# LTE.net
KiCad netlist of a schematic drawn in Altium Designer
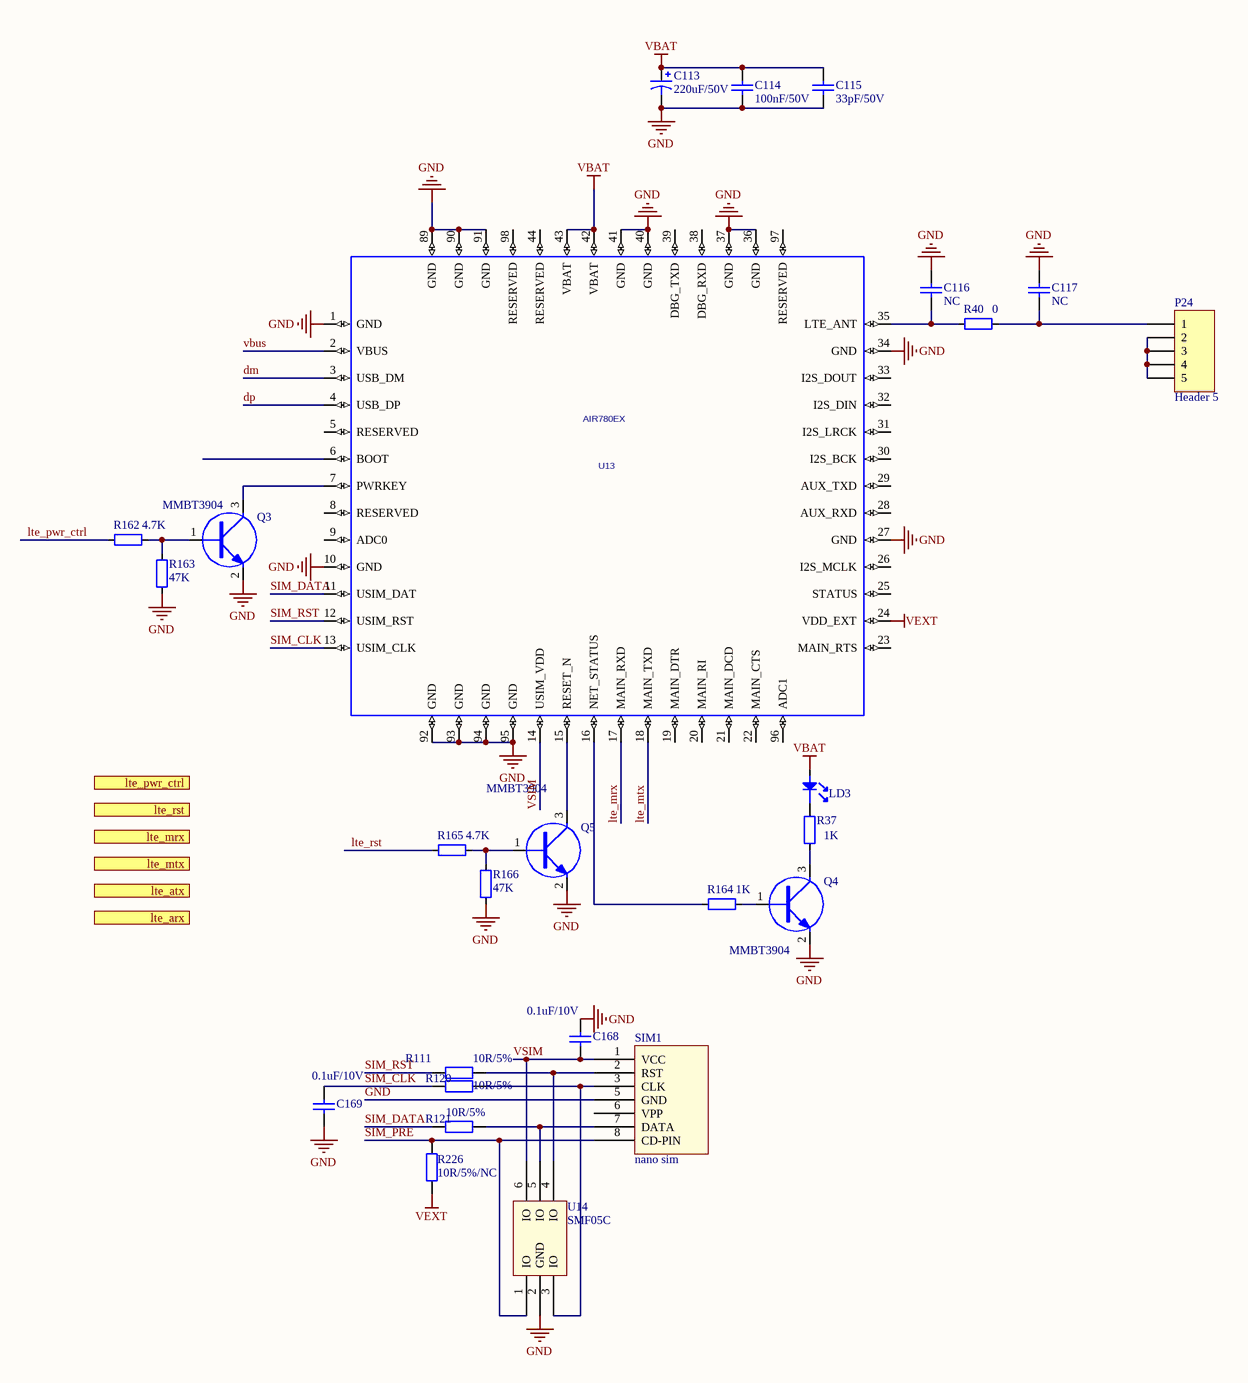
[diagram p0: LTE.SchDoc]

(export (version "E")
  (design (tool "Eeschema 10.0.6"))
  (components
    (comp (ref "C113")
      (value "220uF/50V")
      (footprint "Φ10×10")
      (description "Polarized Capacitor (Radial)")
      (fields (field (name "PUBLISHER") "Altium Limited"))
      (libsource (lib "Miscellaneous Devices") (part "Cap Pol1"))
    )
    (comp (ref "C114")
      (value "100nF/50V")
      (footprint "0603C")
      (description "Capacitor")
      (fields (field (name "PUBLISHER") "Altium Limited"))
      (libsource (lib "Miscellaneous Devices") (part "Cap"))
    )
    (comp (ref "C115")
      (value "33pF/50V")
      (footprint "0603C")
      (description "Capacitor")
      (fields (field (name "PUBLISHER") "Altium Limited"))
      (libsource (lib "Miscellaneous Devices") (part "Cap"))
    )
    (comp (ref "C116")
      (value "NC")
      (footprint "0603c")
      (description "Capacitor")
      (fields (field (name "PUBLISHER") "Altium Limited"))
      (libsource (lib "Miscellaneous Devices") (part "Cap"))
    )
    (comp (ref "C117")
      (value "NC")
      (footprint "0603c")
      (description "Capacitor")
      (fields (field (name "PUBLISHER") "Altium Limited"))
      (libsource (lib "Miscellaneous Devices") (part "Cap"))
    )
    (comp (ref "C168")
      (value "0.1uF/10V")
      (footprint "0603c")
      (description "Capacitor")
      (fields (field (name "PUBLISHER") "Altium Limited"))
      (libsource (lib "Miscellaneous Devices") (part "Cap"))
    )
    (comp (ref "C169")
      (value "0.1uF/10V")
      (footprint "0603c")
      (description "Capacitor")
      (fields (field (name "PUBLISHER") "Altium Limited"))
      (libsource (lib "Miscellaneous Devices") (part "Cap"))
    )
    (comp (ref "LD3")
      (value "LED_Green_19-217")
      (footprint "0603led")
      (libsource (lib "RC_M_D_00") (part "LED_Green_19-217"))
    )
    (comp (ref "P24")
      (value "Header 5")
      (footprint "KH-SMA-KE-Z")
      (description "Header, 5-Pin")
      (fields (field (name "PUBLISHER") "Altium Limited"))
      (libsource (lib "Miscellaneous Connectors") (part "Header 5"))
    )
    (comp (ref "Q3")
      (value "MMBT3904")
      (footprint "SOT23-3")
      (libsource (lib "CenLib") (part "NPN_MMBT3904"))
    )
    (comp (ref "Q4")
      (value "MMBT3904")
      (footprint "SOT23-3")
      (libsource (lib "CenLib") (part "NPN_MMBT3904"))
    )
    (comp (ref "Q5")
      (value "MMBT3904")
      (footprint "SOT23-3")
      (libsource (lib "CenLib") (part "NPN_MMBT3904"))
    )
    (comp (ref "R37") (value "1K") (footprint "0603R") (libsource (lib "RC_M_D_00") (part "RES0603")))
    (comp (ref "R40") (value "0") (footprint "0603r") (libsource (lib "RC_M_D_00") (part "RES0603")))
    (comp (ref "R111")
      (value "10R/5%")
      (footprint "0603r")
      (description "Resistor")
      (fields (field (name "PUBLISHER") "Altium Limited"))
      (libsource (lib "") (part "Res2_1"))
    )
    (comp (ref "R120")
      (value "10R/5%")
      (footprint "0603r")
      (description "Resistor")
      (fields (field (name "PUBLISHER") "Altium Limited"))
      (libsource (lib "") (part "Res2_1"))
    )
    (comp (ref "R121")
      (value "10R/5%")
      (footprint "0603r")
      (description "Resistor")
      (fields (field (name "PUBLISHER") "Altium Limited"))
      (libsource (lib "") (part "Res2_1"))
    )
    (comp (ref "R162") (value "4.7K") (footprint "0603R") (libsource (lib "RC_M_D_00") (part "RES0603")))
    (comp (ref "R163") (value "47K") (footprint "0603r") (libsource (lib "RC_M_D_00") (part "RES0603")))
    (comp (ref "R164") (value "1K") (footprint "0603r") (libsource (lib "RC_M_D_00") (part "RES0603")))
    (comp (ref "R165") (value "4.7K") (footprint "0603R") (libsource (lib "RC_M_D_00") (part "RES0603")))
    (comp (ref "R166") (value "47K") (footprint "0603r") (libsource (lib "RC_M_D_00") (part "RES0603")))
    (comp (ref "R226")
      (value "10R/5%/NC")
      (footprint "0603r")
      (description "Resistor")
      (fields (field (name "PUBLISHER") "Altium Limited"))
      (libsource (lib "Miscellaneous Devices") (part "Res2"))
    )
    (comp (ref "SIM1") (value "nano sim") (footprint "Nano SIM") (libsource (lib "lm") (part "nano sim")))
    (comp (ref "U13")
      (value "AIR780EX")
      (footprint "Air780EX_AD:AIR780EX")
      (libsource (lib "*") (part "AIR780EX"))
    )
    (comp (ref "U14") (value "SMF05C") (footprint "sc70-6l") (libsource (lib "lm") (part "SMF05C")))
  )
  (nets
    (net (code "1") (name "/SIM_CLK") (class "Default")
      (node (ref "C169") (pin "1") (pinfunction "1_1") (pintype "passive"))
      (node (ref "R120") (pin "2") (pinfunction "2_2") (pintype "passive"))
      (node (ref "U13") (pin "13") (pinfunction "USIM_CLK_13") (pintype "bidirectional"))
    )
    (net (code "2") (name "/SIM_DATA") (class "Default")
      (node (ref "R121") (pin "2") (pinfunction "2_2") (pintype "passive"))
      (node (ref "U13") (pin "11") (pinfunction "USIM_DAT_11") (pintype "bidirectional"))
    )
    (net (code "3") (name "/SIM_PRE") (class "Default")
      (node (ref "R226") (pin "1") (pinfunction "1_1") (pintype "passive"))
      (node (ref "SIM1") (pin "8") (pinfunction "CD-PIN_8") (pintype "passive"))
      (node (ref "U14") (pin "1") (pinfunction "IO_1") (pintype "passive"))
    )
    (net (code "4") (name "/SIM_RST") (class "Default")
      (node (ref "R111") (pin "2") (pinfunction "2_2") (pintype "passive"))
      (node (ref "U13") (pin "12") (pinfunction "USIM_RST_12") (pintype "bidirectional"))
    )
    (net (code "5") (name "/VSIM") (class "Default")
      (node (ref "C168") (pin "2") (pinfunction "2_2") (pintype "passive"))
      (node (ref "SIM1") (pin "1") (pinfunction "VCC_1") (pintype "passive"))
      (node (ref "U13") (pin "14") (pinfunction "USIM_VDD_14") (pintype "bidirectional"))
      (node (ref "U14") (pin "6") (pinfunction "IO_6") (pintype "passive"))
    )
    (net (code "6") (name "/dm") (class "Default")
      (node (ref "U13") (pin "3") (pinfunction "USB_DM_3") (pintype "bidirectional"))
    )
    (net (code "7") (name "/dp") (class "Default")
      (node (ref "U13") (pin "4") (pinfunction "USB_DP_4") (pintype "bidirectional"))
    )
    (net (code "10") (name "/lte_mrx") (class "Default")
      (node (ref "U13") (pin "17") (pinfunction "MAIN_RXD_17") (pintype "bidirectional"))
    )
    (net (code "11") (name "/lte_mtx") (class "Default")
      (node (ref "U13") (pin "18") (pinfunction "MAIN_TXD_18") (pintype "bidirectional"))
    )
    (net (code "12") (name "/lte_pwr_ctrl") (class "Default")
      (node (ref "R162") (pin "1") (pinfunction "1_1") (pintype "passive"))
    )
    (net (code "13") (name "/lte_rst") (class "Default")
      (node (ref "R165") (pin "1") (pinfunction "1_1") (pintype "passive"))
    )
    (net (code "14") (name "/vbus") (class "Default")
      (node (ref "U13") (pin "2") (pinfunction "VBUS_2") (pintype "bidirectional"))
    )
    (net (code "15") (name "GND") (class "Default")
      (node (ref "C113") (pin "2") (pinfunction "2_2") (pintype "passive"))
      (node (ref "C114") (pin "1") (pinfunction "1_1") (pintype "passive"))
      (node (ref "C115") (pin "1") (pinfunction "1_1") (pintype "passive"))
      (node (ref "C116") (pin "2") (pinfunction "2_2") (pintype "passive"))
      (node (ref "C117") (pin "2") (pinfunction "2_2") (pintype "passive"))
      (node (ref "C168") (pin "1") (pinfunction "1_1") (pintype "passive"))
      (node (ref "C169") (pin "2") (pinfunction "2_2") (pintype "passive"))
      (node (ref "Q3") (pin "2") (pinfunction "E_2") (pintype "passive"))
      (node (ref "Q4") (pin "2") (pinfunction "E_2") (pintype "passive"))
      (node (ref "Q5") (pin "2") (pinfunction "E_2") (pintype "passive"))
      (node (ref "R163") (pin "1") (pinfunction "1_1") (pintype "passive"))
      (node (ref "R166") (pin "1") (pinfunction "1_1") (pintype "passive"))
      (node (ref "SIM1") (pin "5") (pinfunction "GND_5") (pintype "passive"))
      (node (ref "U13") (pin "1") (pinfunction "GND_1") (pintype "bidirectional"))
      (node (ref "U13") (pin "10") (pinfunction "GND_10") (pintype "bidirectional"))
      (node (ref "U13") (pin "27") (pinfunction "GND_27") (pintype "bidirectional"))
      (node (ref "U13") (pin "34") (pinfunction "GND_34") (pintype "bidirectional"))
      (node (ref "U13") (pin "36") (pinfunction "GND_36") (pintype "bidirectional"))
      (node (ref "U13") (pin "37") (pinfunction "GND_37") (pintype "bidirectional"))
      (node (ref "U13") (pin "40") (pinfunction "GND_40") (pintype "bidirectional"))
      (node (ref "U13") (pin "41") (pinfunction "GND_41") (pintype "bidirectional"))
      (node (ref "U13") (pin "89") (pinfunction "GND_89") (pintype "bidirectional"))
      (node (ref "U13") (pin "90") (pinfunction "GND_90") (pintype "bidirectional"))
      (node (ref "U13") (pin "91") (pinfunction "GND_91") (pintype "bidirectional"))
      (node (ref "U13") (pin "92") (pinfunction "GND_92") (pintype "bidirectional"))
      (node (ref "U13") (pin "93") (pinfunction "GND_93") (pintype "bidirectional"))
      (node (ref "U13") (pin "94") (pinfunction "GND_94") (pintype "bidirectional"))
      (node (ref "U13") (pin "95") (pinfunction "GND_95") (pintype "bidirectional"))
      (node (ref "U14") (pin "2") (pinfunction "GND_2") (pintype "passive"))
    )
    (net (code "16") (name "Net-(C117-Pad1)") (class "Default")
      (node (ref "C117") (pin "1") (pinfunction "1_1") (pintype "passive"))
      (node (ref "P24") (pin "1") (pinfunction "1_1") (pintype "passive"))
      (node (ref "R40") (pin "2") (pinfunction "2_2") (pintype "passive"))
    )
    (net (code "17") (name "Net-(LD3-Pad2)") (class "Default")
      (node (ref "LD3") (pin "2") (pinfunction "2_2") (pintype "passive"))
      (node (ref "R37") (pin "1") (pinfunction "1_1") (pintype "passive"))
    )
    (net (code "18") (name "Net-(P24-Pad2)") (class "Default")
      (node (ref "P24") (pin "2") (pinfunction "2_2") (pintype "passive"))
      (node (ref "P24") (pin "3") (pinfunction "3_3") (pintype "passive"))
      (node (ref "P24") (pin "4") (pinfunction "4_4") (pintype "passive"))
      (node (ref "P24") (pin "5") (pinfunction "5_5") (pintype "passive"))
    )
    (net (code "19") (name "Net-(Q3-B)") (class "Default")
      (node (ref "Q3") (pin "1") (pinfunction "B_1") (pintype "passive"))
      (node (ref "R162") (pin "2") (pinfunction "2_2") (pintype "passive"))
      (node (ref "R163") (pin "2") (pinfunction "2_2") (pintype "passive"))
    )
    (net (code "20") (name "Net-(Q3-C)") (class "Default")
      (node (ref "Q3") (pin "3") (pinfunction "C_3") (pintype "passive"))
      (node (ref "U13") (pin "7") (pinfunction "PWRKEY_7") (pintype "bidirectional"))
    )
    (net (code "21") (name "Net-(Q4-B)") (class "Default")
      (node (ref "Q4") (pin "1") (pinfunction "B_1") (pintype "passive"))
      (node (ref "R164") (pin "2") (pinfunction "2_2") (pintype "passive"))
    )
    (net (code "22") (name "Net-(Q4-C)") (class "Default")
      (node (ref "Q4") (pin "3") (pinfunction "C_3") (pintype "passive"))
      (node (ref "R37") (pin "2") (pinfunction "2_2") (pintype "passive"))
    )
    (net (code "23") (name "Net-(Q5-B)") (class "Default")
      (node (ref "Q5") (pin "1") (pinfunction "B_1") (pintype "passive"))
      (node (ref "R165") (pin "2") (pinfunction "2_2") (pintype "passive"))
      (node (ref "R166") (pin "2") (pinfunction "2_2") (pintype "passive"))
    )
    (net (code "24") (name "Net-(Q5-C)") (class "Default")
      (node (ref "Q5") (pin "3") (pinfunction "C_3") (pintype "passive"))
      (node (ref "U13") (pin "15") (pinfunction "RESET_N_15") (pintype "bidirectional"))
    )
    (net (code "25") (name "Net-(SIM1-CLK)") (class "Default")
      (node (ref "R120") (pin "1") (pinfunction "1_1") (pintype "passive"))
      (node (ref "SIM1") (pin "3") (pinfunction "CLK_3") (pintype "passive"))
      (node (ref "U14") (pin "3") (pinfunction "IO_3") (pintype "passive"))
    )
    (net (code "26") (name "Net-(SIM1-DATA)") (class "Default")
      (node (ref "R121") (pin "1") (pinfunction "1_1") (pintype "passive"))
      (node (ref "SIM1") (pin "7") (pinfunction "DATA_7") (pintype "passive"))
      (node (ref "U14") (pin "5") (pinfunction "IO_5") (pintype "passive"))
    )
    (net (code "27") (name "Net-(SIM1-RST)") (class "Default")
      (node (ref "R111") (pin "1") (pinfunction "1_1") (pintype "passive"))
      (node (ref "SIM1") (pin "2") (pinfunction "RST_2") (pintype "passive"))
      (node (ref "U14") (pin "4") (pinfunction "IO_4") (pintype "passive"))
    )
    (net (code "28") (name "Net-(U13-LTE_ANT)") (class "Default")
      (node (ref "C116") (pin "1") (pinfunction "1_1") (pintype "passive"))
      (node (ref "R40") (pin "1") (pinfunction "1_1") (pintype "passive"))
      (node (ref "U13") (pin "35") (pinfunction "LTE_ANT_35") (pintype "bidirectional"))
    )
    (net (code "29") (name "Net-(U13-NET_STATUS)") (class "Default")
      (node (ref "R164") (pin "1") (pinfunction "1_1") (pintype "passive"))
      (node (ref "U13") (pin "16") (pinfunction "NET_STATUS_16") (pintype "bidirectional"))
    )
    (net (code "30") (name "VBAT") (class "Default")
      (node (ref "C113") (pin "1") (pinfunction "1_1") (pintype "passive"))
      (node (ref "C114") (pin "2") (pinfunction "2_2") (pintype "passive"))
      (node (ref "C115") (pin "2") (pinfunction "2_2") (pintype "passive"))
      (node (ref "LD3") (pin "1") (pinfunction "1_1") (pintype "passive"))
      (node (ref "U13") (pin "42") (pinfunction "VBAT_42") (pintype "bidirectional"))
      (node (ref "U13") (pin "43") (pinfunction "VBAT_43") (pintype "bidirectional"))
    )
    (net (code "31") (name "VEXT") (class "Default")
      (node (ref "R226") (pin "2") (pinfunction "2_2") (pintype "passive"))
      (node (ref "U13") (pin "24") (pinfunction "VDD_EXT_24") (pintype "bidirectional"))
    )
    (net (code "32") (name "unconnected-(SIM1-VPP-Pad6)") (class "Default")
      (node (ref "SIM1") (pin "6") (pinfunction "VPP_6") (pintype "passive"))
    )
    (net (code "33") (name "unconnected-(U13-ADC0-Pad9)") (class "Default")
      (node (ref "U13") (pin "9") (pinfunction "ADC0_9") (pintype "bidirectional"))
    )
    (net (code "34") (name "unconnected-(U13-ADC1-Pad96)") (class "Default")
      (node (ref "U13") (pin "96") (pinfunction "ADC1_96") (pintype "bidirectional"))
    )
    (net (code "35") (name "unconnected-(U13-AUX_RXD-Pad28)") (class "Default")
      (node (ref "U13") (pin "28") (pinfunction "AUX_RXD_28") (pintype "bidirectional"))
    )
    (net (code "36") (name "unconnected-(U13-AUX_TXD-Pad29)") (class "Default")
      (node (ref "U13") (pin "29") (pinfunction "AUX_TXD_29") (pintype "bidirectional"))
    )
    (net (code "37") (name "unconnected-(U13-BOOT-Pad6)") (class "Default")
      (node (ref "U13") (pin "6") (pinfunction "BOOT_6") (pintype "bidirectional"))
    )
    (net (code "38") (name "unconnected-(U13-DBG_RXD-Pad38)") (class "Default")
      (node (ref "U13") (pin "38") (pinfunction "DBG_RXD_38") (pintype "bidirectional"))
    )
    (net (code "39") (name "unconnected-(U13-DBG_TXD-Pad39)") (class "Default")
      (node (ref "U13") (pin "39") (pinfunction "DBG_TXD_39") (pintype "bidirectional"))
    )
    (net (code "40") (name "unconnected-(U13-I2S_BCK-Pad30)") (class "Default")
      (node (ref "U13") (pin "30") (pinfunction "I2S_BCK_30") (pintype "bidirectional"))
    )
    (net (code "41") (name "unconnected-(U13-I2S_DIN-Pad32)") (class "Default")
      (node (ref "U13") (pin "32") (pinfunction "I2S_DIN_32") (pintype "bidirectional"))
    )
    (net (code "42") (name "unconnected-(U13-I2S_DOUT-Pad33)") (class "Default")
      (node (ref "U13") (pin "33") (pinfunction "I2S_DOUT_33") (pintype "bidirectional"))
    )
    (net (code "43") (name "unconnected-(U13-I2S_LRCK-Pad31)") (class "Default")
      (node (ref "U13") (pin "31") (pinfunction "I2S_LRCK_31") (pintype "bidirectional"))
    )
    (net (code "44") (name "unconnected-(U13-I2S_MCLK-Pad26)") (class "Default")
      (node (ref "U13") (pin "26") (pinfunction "I2S_MCLK_26") (pintype "bidirectional"))
    )
    (net (code "45") (name "unconnected-(U13-MAIN_CTS-Pad22)") (class "Default")
      (node (ref "U13") (pin "22") (pinfunction "MAIN_CTS_22") (pintype "bidirectional"))
    )
    (net (code "46") (name "unconnected-(U13-MAIN_DCD-Pad21)") (class "Default")
      (node (ref "U13") (pin "21") (pinfunction "MAIN_DCD_21") (pintype "bidirectional"))
    )
    (net (code "47") (name "unconnected-(U13-MAIN_DTR-Pad19)") (class "Default")
      (node (ref "U13") (pin "19") (pinfunction "MAIN_DTR_19") (pintype "bidirectional"))
    )
    (net (code "48") (name "unconnected-(U13-MAIN_RI-Pad20)") (class "Default")
      (node (ref "U13") (pin "20") (pinfunction "MAIN_RI_20") (pintype "bidirectional"))
    )
    (net (code "49") (name "unconnected-(U13-MAIN_RTS-Pad23)") (class "Default")
      (node (ref "U13") (pin "23") (pinfunction "MAIN_RTS_23") (pintype "bidirectional"))
    )
    (net (code "50") (name "unconnected-(U13-RESERVED-Pad5)") (class "Default")
      (node (ref "U13") (pin "5") (pinfunction "RESERVED_5") (pintype "bidirectional"))
    )
    (net (code "51") (name "unconnected-(U13-RESERVED-Pad8)") (class "Default")
      (node (ref "U13") (pin "8") (pinfunction "RESERVED_8") (pintype "bidirectional"))
    )
    (net (code "52") (name "unconnected-(U13-RESERVED-Pad44)") (class "Default")
      (node (ref "U13") (pin "44") (pinfunction "RESERVED_44") (pintype "bidirectional"))
    )
    (net (code "53") (name "unconnected-(U13-RESERVED-Pad97)") (class "Default")
      (node (ref "U13") (pin "97") (pinfunction "RESERVED_97") (pintype "bidirectional"))
    )
    (net (code "54") (name "unconnected-(U13-RESERVED-Pad98)") (class "Default")
      (node (ref "U13") (pin "98") (pinfunction "RESERVED_98") (pintype "bidirectional"))
    )
    (net (code "55") (name "unconnected-(U13-STATUS-Pad25)") (class "Default")
      (node (ref "U13") (pin "25") (pinfunction "STATUS_25") (pintype "bidirectional"))
    )
  )
)
